# BuckRegulator-3V.net
KiCad netlist of a schematic drawn in Altium Designer
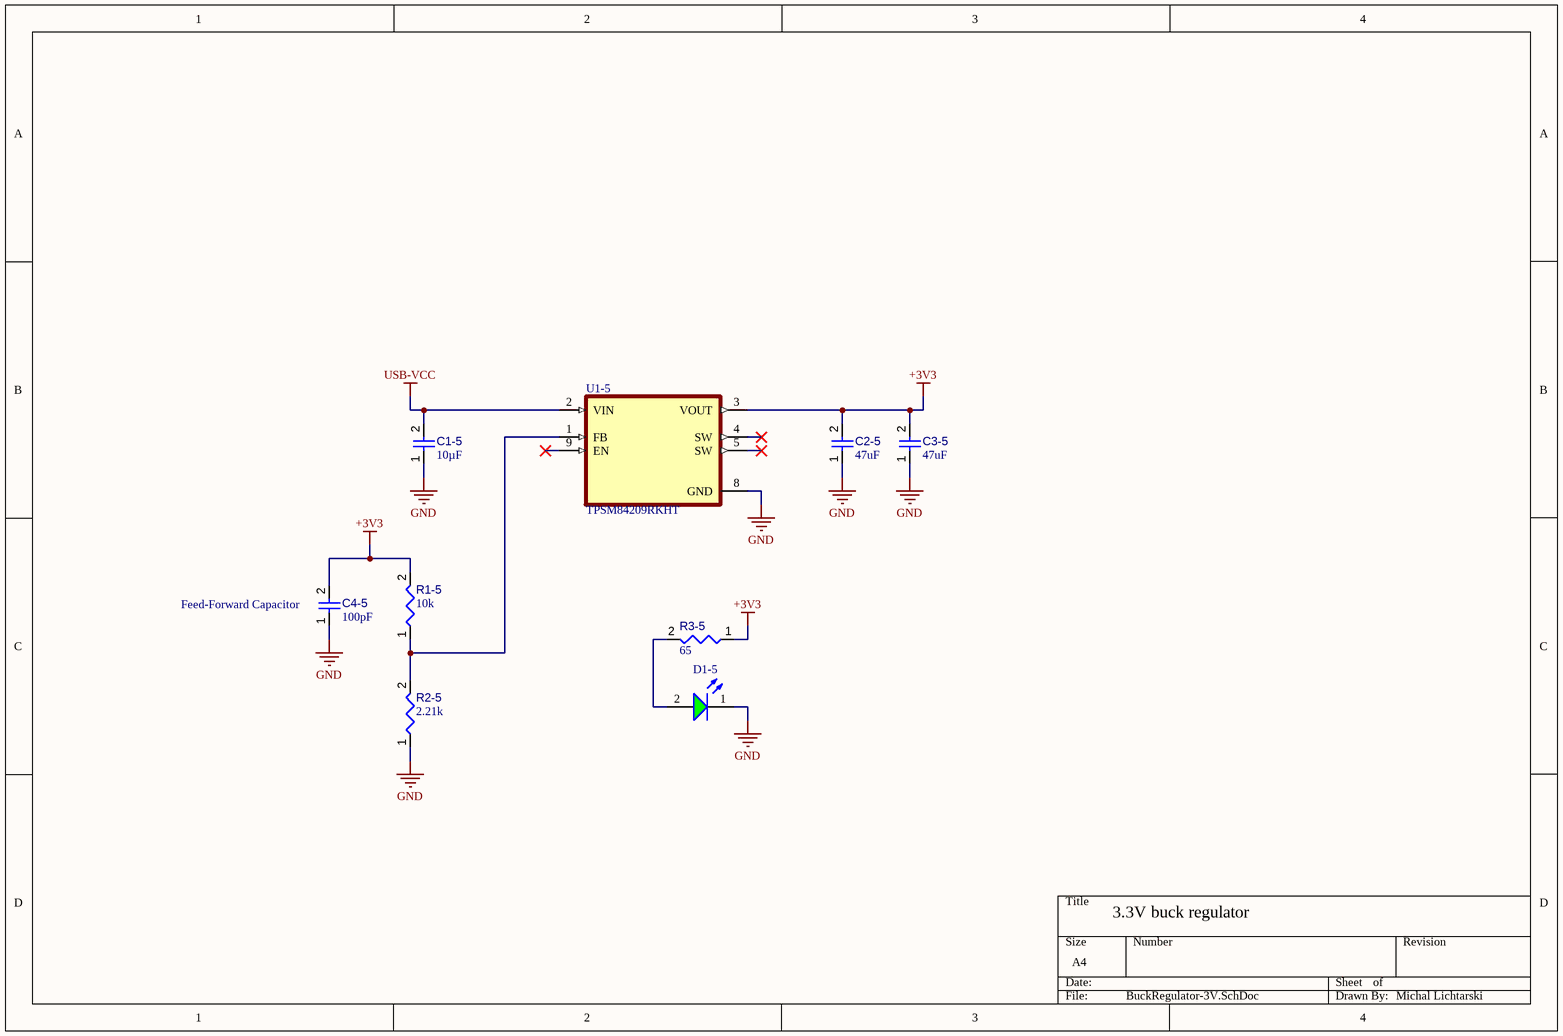
[diagram p0: BuckRegulator-3V.SchDoc]

(export (version "E")
  (design (tool "Eeschema 10.0.6"))
  (components
    (comp (ref "C1-5")
      (value "10µF")
      (footprint "CAPC3216X180X50NL20T25")
      (fields (field (name "TOLERANCE") "10%") (field (name "Comment") "10uF 0603"))
      (libsource (lib "Michal") (part "CAP-NP-2"))
    )
    (comp (ref "C2-5")
      (value "47uF")
      (footprint "CAPC1608X94X35NL15T15")
      (fields (field (name "TOLERANCE") "10%") (field (name "Comment") "47uF 0603"))
      (libsource (lib "Michal") (part "CAP-NP-2"))
    )
    (comp (ref "C3-5")
      (value "47uF")
      (footprint "CAPC1608X94X35NL15T15")
      (fields (field (name "TOLERANCE") "10%") (field (name "Comment") "47uF 0603"))
      (libsource (lib "Michal") (part "CAP-NP-2"))
    )
    (comp (ref "C4-5")
      (value "100pF")
      (footprint "CAPC1608X94X35NL15T15")
      (fields (field (name "TOLERANCE") "10%") (field (name "Comment") "100pF 0603"))
      (libsource (lib "Michal") (part "CAP-NP-2"))
    )
    (comp (ref "D1-5")
      (value "150060VS75000")
      (footprint "WL-SMCW_0603_150060xx75000")
      (libsource (lib "Altium Content Vault") (part "LED_Green_2A-1K"))
    )
    (comp (ref "R1-5")
      (value "10k")
      (footprint "RESC1608X55X25ML10T15")
      (fields (field (name "TOLERANCE") "1%") (field (name "POWER") "100mW"))
      (libsource (lib "Michal") (part "RES-2"))
    )
    (comp (ref "R2-5")
      (value "2.21k")
      (footprint "RESC1608X55X25ML10T15")
      (fields (field (name "TOLERANCE") "1%") (field (name "POWER") "100mW"))
      (libsource (lib "Michal") (part "RES-2"))
    )
    (comp (ref "R3-5")
      (value "65")
      (footprint "RESC1608X55X25ML10T15")
      (fields (field (name "TOLERANCE") "1%") (field (name "POWER") "100mW"))
      (libsource (lib "Michal") (part "RES-2"))
    )
    (comp (ref "U1-5")
      (value "TPSM84209RKHT")
      (footprint "VREG_TPSM84209RKHT")
      (fields (field (name "MF") "{'manufacturer': u'Texas Instruments'}"))
      (libsource (lib "TPSM84209RKHT") (part "TPSM84209RKHT"))
    )
  )
  (nets
    (net (code "1") (name "+3V3") (class "Default")
      (node (ref "C2-5") (pin "2") (pinfunction "2_2") (pintype "passive"))
      (node (ref "C3-5") (pin "2") (pinfunction "2_2") (pintype "passive"))
      (node (ref "C4-5") (pin "2") (pinfunction "2_2") (pintype "passive"))
      (node (ref "R1-5") (pin "2") (pinfunction "2_2") (pintype "passive"))
      (node (ref "R3-5") (pin "1") (pinfunction "1_1") (pintype "passive"))
      (node (ref "U1-5") (pin "3") (pinfunction "VOUT_3") (pintype "output"))
    )
    (net (code "2") (name "GND") (class "Default")
      (node (ref "C1-5") (pin "1") (pinfunction "1_1") (pintype "passive"))
      (node (ref "C2-5") (pin "1") (pinfunction "1_1") (pintype "passive"))
      (node (ref "C3-5") (pin "1") (pinfunction "1_1") (pintype "passive"))
      (node (ref "C4-5") (pin "1") (pinfunction "1_1") (pintype "passive"))
      (node (ref "D1-5") (pin "1") (pinfunction "K_1") (pintype "passive"))
      (node (ref "R2-5") (pin "1") (pinfunction "1_1") (pintype "passive"))
      (node (ref "U1-5") (pin "8") (pinfunction "GND_8") (pintype "power_in"))
    )
    (net (code "3") (name "Net-(D1-5-A)") (class "Default")
      (node (ref "D1-5") (pin "2") (pinfunction "A_2") (pintype "passive"))
      (node (ref "R3-5") (pin "2") (pinfunction "2_2") (pintype "passive"))
    )
    (net (code "4") (name "Net-(U1-5-FB)") (class "Default")
      (node (ref "R1-5") (pin "1") (pinfunction "1_1") (pintype "passive"))
      (node (ref "R2-5") (pin "2") (pinfunction "2_2") (pintype "passive"))
      (node (ref "U1-5") (pin "1") (pinfunction "FB_1") (pintype "input"))
    )
    (net (code "5") (name "USB-VCC") (class "Default")
      (node (ref "C1-5") (pin "2") (pinfunction "2_2") (pintype "passive"))
      (node (ref "U1-5") (pin "2") (pinfunction "VIN_2") (pintype "input"))
    )
    (net (code "6") (name "unconnected-(U1-5-EN-Pad9)") (class "Default")
      (node (ref "U1-5") (pin "9") (pinfunction "EN_9") (pintype "input+no_connect"))
    )
    (net (code "7") (name "unconnected-(U1-5-SW-Pad4)") (class "Default")
      (node (ref "U1-5") (pin "4") (pinfunction "SW_4") (pintype "output+no_connect"))
    )
    (net (code "8") (name "unconnected-(U1-5-SW-Pad5)") (class "Default")
      (node (ref "U1-5") (pin "5") (pinfunction "SW_5") (pintype "output+no_connect"))
    )
  )
)
